# ideal_V2_0.net
KiCad netlist of a schematic drawn in Altium Designer
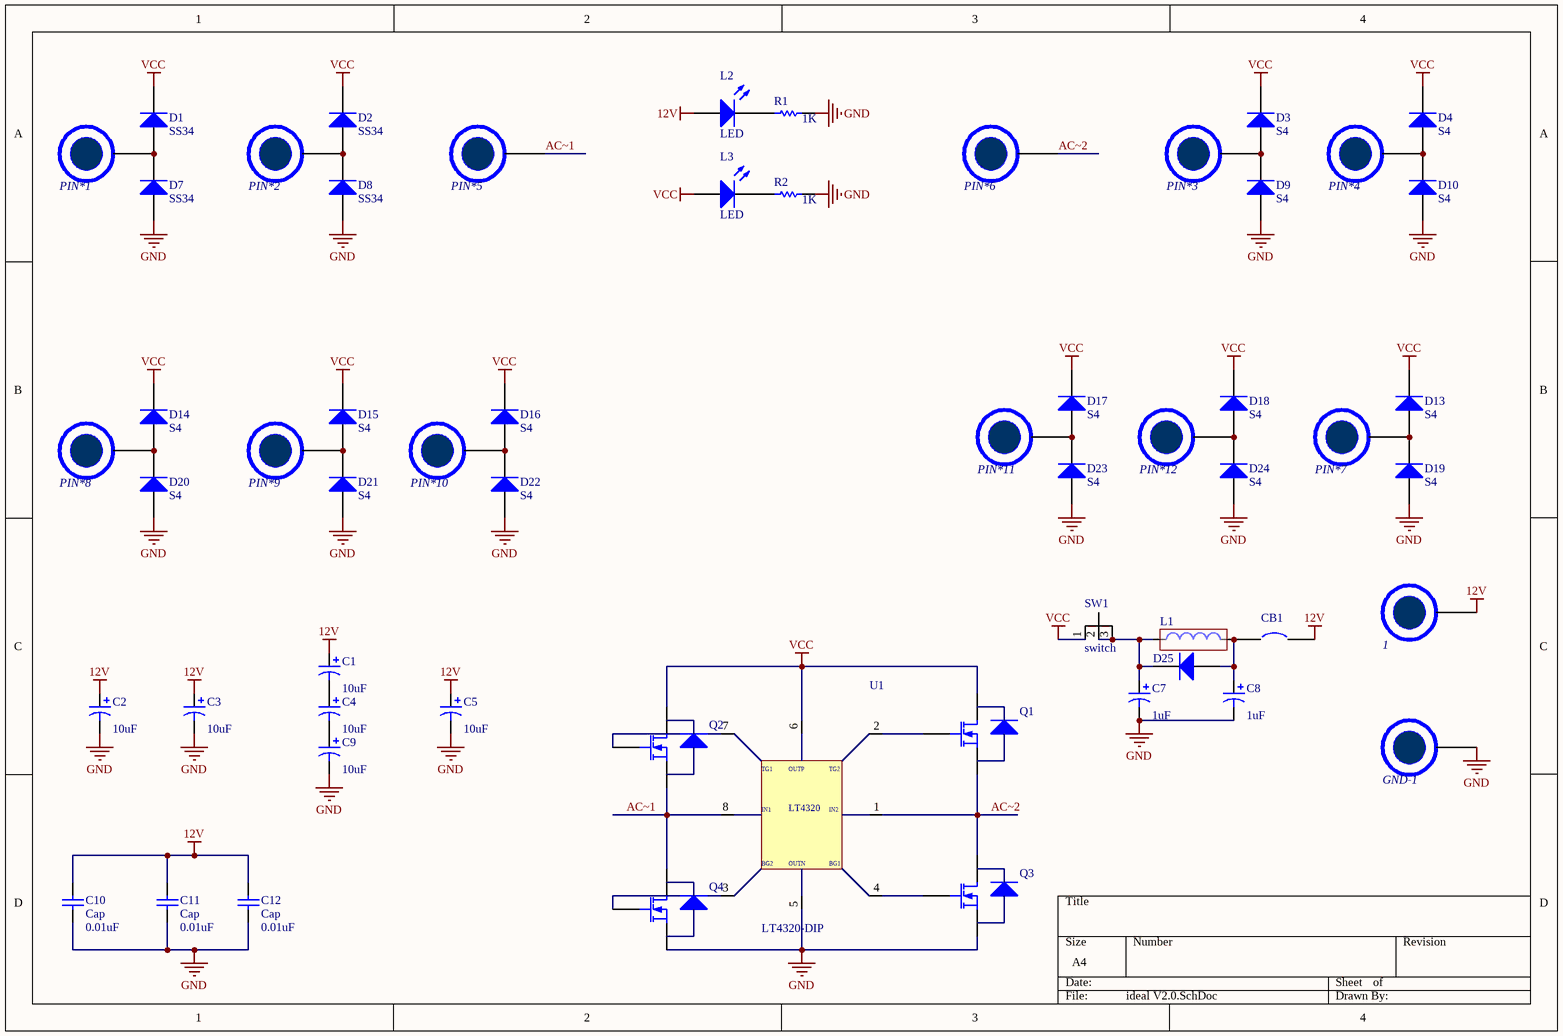
[diagram p0: ideal V2.0.SchDoc]

(export (version "E")
  (design (tool "Eeschema 10.0.6"))
  (components
    (comp (ref "1") (value "PIN") (footprint "PIN") (libsource (lib "常用元件库") (part "PIN")))
    (comp (ref "C1")
      (value "10uF")
      (footprint "法拉电容")
      (description "Polarized Capacitor (Radial)")
      (fields (field (name "Comment") "Cap Pol1") (field (name "PUBLISHER") "Altium Limited"))
      (libsource (lib "Miscellaneous Devices") (part "Cap Pol1"))
    )
    (comp (ref "C2")
      (value "10uF")
      (footprint "RB7.6-15")
      (description "Polarized Capacitor (Radial)")
      (fields (field (name "Comment") "Cap Pol1") (field (name "PUBLISHER") "Altium Limited"))
      (libsource (lib "Miscellaneous Devices") (part "Cap Pol1"))
    )
    (comp (ref "C3")
      (value "10uF")
      (footprint "RB7.6-15")
      (description "Polarized Capacitor (Radial)")
      (fields (field (name "Comment") "Cap Pol1") (field (name "PUBLISHER") "Altium Limited"))
      (libsource (lib "Miscellaneous Devices") (part "Cap Pol1"))
    )
    (comp (ref "C4")
      (value "10uF")
      (footprint "法拉电容")
      (description "Polarized Capacitor (Radial)")
      (fields (field (name "Comment") "Cap Pol1") (field (name "PUBLISHER") "Altium Limited"))
      (libsource (lib "Miscellaneous Devices") (part "Cap Pol1"))
    )
    (comp (ref "C5")
      (value "10uF")
      (footprint "RB7.6-15")
      (description "Polarized Capacitor (Radial)")
      (fields (field (name "Comment") "Cap Pol1") (field (name "PUBLISHER") "Altium Limited"))
      (libsource (lib "Miscellaneous Devices") (part "Cap Pol1"))
    )
    (comp (ref "C7")
      (value "1uF")
      (footprint "C2012")
      (description "Polarized Capacitor (Radial)")
      (fields (field (name "Comment") "Cap Pol1") (field (name "PUBLISHER") "Altium Limited"))
      (libsource (lib "Miscellaneous Devices") (part "Cap Pol1"))
    )
    (comp (ref "C8")
      (value "1uF")
      (footprint "C2012")
      (description "Polarized Capacitor (Radial)")
      (fields (field (name "Comment") "Cap Pol1") (field (name "PUBLISHER") "Altium Limited"))
      (libsource (lib "Miscellaneous Devices") (part "Cap Pol1"))
    )
    (comp (ref "C9")
      (value "10uF")
      (footprint "法拉电容")
      (description "Polarized Capacitor (Radial)")
      (fields (field (name "Comment") "Cap Pol1") (field (name "PUBLISHER") "Altium Limited"))
      (libsource (lib "Miscellaneous Devices") (part "Cap Pol1"))
    )
    (comp (ref "C10")
      (value "Cap")
      (footprint "C2012")
      (description "Capacitor")
      (fields (field (name "ALTIUM_VALUE") "0.01uF") (field (name "PUBLISHER") "Altium Limited"))
      (libsource (lib "Miscellaneous Devices") (part "Cap"))
    )
    (comp (ref "C11")
      (value "Cap")
      (footprint "C2012")
      (description "Capacitor")
      (fields (field (name "ALTIUM_VALUE") "0.01uF") (field (name "PUBLISHER") "Altium Limited"))
      (libsource (lib "Miscellaneous Devices") (part "Cap"))
    )
    (comp (ref "C12")
      (value "Cap")
      (footprint "C2012")
      (description "Capacitor")
      (fields (field (name "ALTIUM_VALUE") "0.01uF") (field (name "PUBLISHER") "Altium Limited"))
      (libsource (lib "Miscellaneous Devices") (part "Cap"))
    )
    (comp (ref "CB1")
      (value "Circuit Breaker")
      (footprint "SPST-2")
      (fields (field (name "PUBLISHER") "Altium Limited"))
      (libsource (lib "Miscellaneous Devices") (part "Circuit Breaker"))
    )
    (comp (ref "D1")
      (value "SS34")
      (footprint "1206(2)")
      (description "High Conductance Fast Diode")
      (fields (field (name "PUBLISHER") "Altium Limited"))
      (libsource (lib "K60-V4.0") (part "Diode 1N4148"))
    )
    (comp (ref "D2")
      (value "SS34")
      (footprint "1206(2)")
      (description "High Conductance Fast Diode")
      (fields (field (name "PUBLISHER") "Altium Limited"))
      (libsource (lib "K60-V4.0") (part "Diode 1N4148"))
    )
    (comp (ref "D3")
      (value "S4")
      (footprint "1206(2)")
      (description "High Conductance Fast Diode")
      (fields (field (name "PUBLISHER") "Altium Limited"))
      (libsource (lib "K60-V4.0") (part "Diode 1N4148"))
    )
    (comp (ref "D4")
      (value "S4")
      (footprint "1206(2)")
      (description "High Conductance Fast Diode")
      (fields (field (name "PUBLISHER") "Altium Limited"))
      (libsource (lib "K60-V4.0") (part "Diode 1N4148"))
    )
    (comp (ref "D7")
      (value "SS34")
      (footprint "1206(2)")
      (description "High Conductance Fast Diode")
      (fields (field (name "PUBLISHER") "Altium Limited"))
      (libsource (lib "K60-V4.0") (part "Diode 1N4148"))
    )
    (comp (ref "D8")
      (value "SS34")
      (footprint "1206(2)")
      (description "High Conductance Fast Diode")
      (fields (field (name "PUBLISHER") "Altium Limited"))
      (libsource (lib "K60-V4.0") (part "Diode 1N4148"))
    )
    (comp (ref "D9")
      (value "S4")
      (footprint "1206(2)")
      (description "High Conductance Fast Diode")
      (fields (field (name "PUBLISHER") "Altium Limited"))
      (libsource (lib "K60-V4.0") (part "Diode 1N4148"))
    )
    (comp (ref "D10")
      (value "S4")
      (footprint "1206(2)")
      (description "High Conductance Fast Diode")
      (fields (field (name "PUBLISHER") "Altium Limited"))
      (libsource (lib "K60-V4.0") (part "Diode 1N4148"))
    )
    (comp (ref "D13")
      (value "S4")
      (footprint "1206(2)")
      (description "High Conductance Fast Diode")
      (fields (field (name "PUBLISHER") "Altium Limited"))
      (libsource (lib "K60-V4.0") (part "Diode 1N4148"))
    )
    (comp (ref "D14")
      (value "S4")
      (footprint "1206(2)")
      (description "High Conductance Fast Diode")
      (fields (field (name "PUBLISHER") "Altium Limited"))
      (libsource (lib "K60-V4.0") (part "Diode 1N4148"))
    )
    (comp (ref "D15")
      (value "S4")
      (footprint "1206(2)")
      (description "High Conductance Fast Diode")
      (fields (field (name "PUBLISHER") "Altium Limited"))
      (libsource (lib "K60-V4.0") (part "Diode 1N4148"))
    )
    (comp (ref "D16")
      (value "S4")
      (footprint "1206(2)")
      (description "High Conductance Fast Diode")
      (fields (field (name "PUBLISHER") "Altium Limited"))
      (libsource (lib "K60-V4.0") (part "Diode 1N4148"))
    )
    (comp (ref "D17")
      (value "S4")
      (footprint "1206(2)")
      (description "High Conductance Fast Diode")
      (fields (field (name "PUBLISHER") "Altium Limited"))
      (libsource (lib "K60-V4.0") (part "Diode 1N4148"))
    )
    (comp (ref "D18")
      (value "S4")
      (footprint "1206(2)")
      (description "High Conductance Fast Diode")
      (fields (field (name "PUBLISHER") "Altium Limited"))
      (libsource (lib "K60-V4.0") (part "Diode 1N4148"))
    )
    (comp (ref "D19")
      (value "S4")
      (footprint "1206(2)")
      (description "High Conductance Fast Diode")
      (fields (field (name "PUBLISHER") "Altium Limited"))
      (libsource (lib "K60-V4.0") (part "Diode 1N4148"))
    )
    (comp (ref "D20")
      (value "S4")
      (footprint "1206(2)")
      (description "High Conductance Fast Diode")
      (fields (field (name "PUBLISHER") "Altium Limited"))
      (libsource (lib "K60-V4.0") (part "Diode 1N4148"))
    )
    (comp (ref "D21")
      (value "S4")
      (footprint "1206(2)")
      (description "High Conductance Fast Diode")
      (fields (field (name "PUBLISHER") "Altium Limited"))
      (libsource (lib "K60-V4.0") (part "Diode 1N4148"))
    )
    (comp (ref "D22")
      (value "S4")
      (footprint "1206(2)")
      (description "High Conductance Fast Diode")
      (fields (field (name "PUBLISHER") "Altium Limited"))
      (libsource (lib "K60-V4.0") (part "Diode 1N4148"))
    )
    (comp (ref "D23")
      (value "S4")
      (footprint "1206(2)")
      (description "High Conductance Fast Diode")
      (fields (field (name "PUBLISHER") "Altium Limited"))
      (libsource (lib "K60-V4.0") (part "Diode 1N4148"))
    )
    (comp (ref "D24")
      (value "S4")
      (footprint "1206(2)")
      (description "High Conductance Fast Diode")
      (fields (field (name "PUBLISHER") "Altium Limited"))
      (libsource (lib "K60-V4.0") (part "Diode 1N4148"))
    )
    (comp (ref "D25")
      (value "Diode 1N4001")
      (footprint "SK54")
      (description "1 Amp General Purpose Rectifier")
      (fields (field (name "PUBLISHER") "Altium Limited"))
      (libsource (lib "Miscellaneous Devices") (part "Diode 1N4001"))
    )
    (comp (ref "GND-1") (value "PIN") (footprint "PIN") (libsource (lib "常用元件库") (part "PIN")))
    (comp (ref "L1")
      (value "33uH")
      (footprint "SMD-EC-F16")
      (description "Inductor")
      (libsource (lib "Landzo") (part "Inductor"))
    )
    (comp (ref "L2") (value "LED") (footprint "C2012") (libsource (lib "Sparks") (part "LED")))
    (comp (ref "L3") (value "LED") (footprint "C2012") (libsource (lib "Sparks") (part "LED")))
    (comp (ref "PIN*1") (value "PIN") (footprint "PIN") (libsource (lib "2号库") (part "PIN")))
    (comp (ref "PIN*2") (value "PIN") (footprint "PIN") (libsource (lib "2号库") (part "PIN")))
    (comp (ref "PIN*3") (value "PIN") (footprint "PIN") (libsource (lib "2号库") (part "PIN")))
    (comp (ref "PIN*4") (value "PIN") (footprint "PIN") (libsource (lib "2号库") (part "PIN")))
    (comp (ref "PIN*5") (value "PIN") (footprint "PIN") (libsource (lib "2号库") (part "PIN")))
    (comp (ref "PIN*6") (value "PIN") (footprint "PIN") (libsource (lib "2号库") (part "PIN")))
    (comp (ref "PIN*7") (value "PIN") (footprint "PIN") (libsource (lib "2号库") (part "PIN")))
    (comp (ref "PIN*8") (value "PIN") (footprint "PIN") (libsource (lib "2号库") (part "PIN")))
    (comp (ref "PIN*9") (value "PIN") (footprint "PIN") (libsource (lib "2号库") (part "PIN")))
    (comp (ref "PIN*10") (value "PIN") (footprint "PIN") (libsource (lib "2号库") (part "PIN")))
    (comp (ref "PIN*11") (value "PIN") (footprint "PIN") (libsource (lib "2号库") (part "PIN")))
    (comp (ref "PIN*12") (value "PIN") (footprint "PIN") (libsource (lib "2号库") (part "PIN")))
    (comp (ref "Q1")
      (value "MOSFET-N")
      (footprint "mos")
      (description "N-Channel MOSFET")
      (fields (field (name "PUBLISHER") "Altium Limited"))
      (libsource (lib "原理图") (part "MOSFET-N"))
    )
    (comp (ref "Q2")
      (value "MOSFET-N")
      (footprint "mos")
      (description "N-Channel MOSFET")
      (fields (field (name "PUBLISHER") "Altium Limited"))
      (libsource (lib "原理图") (part "MOSFET-N"))
    )
    (comp (ref "Q3")
      (value "MOSFET-N")
      (footprint "mos")
      (description "N-Channel MOSFET")
      (fields (field (name "PUBLISHER") "Altium Limited"))
      (libsource (lib "原理图") (part "MOSFET-N"))
    )
    (comp (ref "Q4")
      (value "MOSFET-N")
      (footprint "mos")
      (description "N-Channel MOSFET")
      (fields (field (name "PUBLISHER") "Altium Limited"))
      (libsource (lib "原理图") (part "MOSFET-N"))
    )
    (comp (ref "R1")
      (value "1K")
      (footprint "R2012")
      (description "贴片电阻")
      (fields (field (name "Comment") "Res") (field (name "PUBLISHER") "Altium Limited"))
      (libsource (lib "Sparks") (part "Res"))
    )
    (comp (ref "R2")
      (value "1K")
      (footprint "R2012")
      (description "贴片电阻")
      (fields (field (name "Comment") "Res") (field (name "PUBLISHER") "Altium Limited"))
      (libsource (lib "Sparks") (part "Res"))
    )
    (comp (ref "SW1")
      (value "switch")
      (footprint "SW-125V6A(-)")
      (libsource (lib "2号库") (part "small switch"))
    )
    (comp (ref "U1") (value "LT4320-DIP") (footprint "DIP-8") (libsource (lib "2号库") (part "LT4320-DIP")))
  )
  (nets
    (net (code "1") (name "/AC~1") (class "Default")
      (node (ref "PIN*5") (pin "1") (pinfunction "PIN_1") (pintype "passive"))
      (node (ref "Q2") (pin "3") (pinfunction "S_3") (pintype "passive"))
      (node (ref "Q4") (pin "2") (pinfunction "D_2") (pintype "passive"))
      (node (ref "U1") (pin "8") (pinfunction "8_8") (pintype "passive"))
    )
    (net (code "2") (name "/AC~2") (class "Default")
      (node (ref "PIN*6") (pin "1") (pinfunction "PIN_1") (pintype "passive"))
      (node (ref "Q1") (pin "3") (pinfunction "S_3") (pintype "passive"))
      (node (ref "Q3") (pin "2") (pinfunction "D_2") (pintype "passive"))
      (node (ref "U1") (pin "1") (pinfunction "1_1") (pintype "passive"))
    )
    (net (code "3") (name "12V") (class "Default")
      (node (ref "1") (pin "1") (pinfunction "PIN_1") (pintype "passive"))
      (node (ref "C1") (pin "1") (pinfunction "1_1") (pintype "passive"))
      (node (ref "C10") (pin "2") (pinfunction "2_2") (pintype "passive"))
      (node (ref "C11") (pin "2") (pinfunction "2_2") (pintype "passive"))
      (node (ref "C12") (pin "2") (pinfunction "2_2") (pintype "passive"))
      (node (ref "C2") (pin "1") (pinfunction "1_1") (pintype "passive"))
      (node (ref "C3") (pin "1") (pinfunction "1_1") (pintype "passive"))
      (node (ref "C5") (pin "1") (pinfunction "1_1") (pintype "passive"))
      (node (ref "CB1") (pin "2") (pinfunction "2_2") (pintype "passive"))
      (node (ref "L2") (pin "1") (pinfunction "A_1") (pintype "passive"))
    )
    (net (code "4") (name "GND") (class "Default")
      (node (ref "C10") (pin "1") (pinfunction "1_1") (pintype "passive"))
      (node (ref "C11") (pin "1") (pinfunction "1_1") (pintype "passive"))
      (node (ref "C12") (pin "1") (pinfunction "1_1") (pintype "passive"))
      (node (ref "C2") (pin "2") (pinfunction "2_2") (pintype "passive"))
      (node (ref "C3") (pin "2") (pinfunction "2_2") (pintype "passive"))
      (node (ref "C5") (pin "2") (pinfunction "2_2") (pintype "passive"))
      (node (ref "C7") (pin "2") (pinfunction "2_2") (pintype "passive"))
      (node (ref "C8") (pin "2") (pinfunction "2_2") (pintype "passive"))
      (node (ref "C9") (pin "2") (pinfunction "2_2") (pintype "passive"))
      (node (ref "D10") (pin "1") (pinfunction "A_1") (pintype "passive"))
      (node (ref "D19") (pin "1") (pinfunction "A_1") (pintype "passive"))
      (node (ref "D20") (pin "1") (pinfunction "A_1") (pintype "passive"))
      (node (ref "D21") (pin "1") (pinfunction "A_1") (pintype "passive"))
      (node (ref "D22") (pin "1") (pinfunction "A_1") (pintype "passive"))
      (node (ref "D23") (pin "1") (pinfunction "A_1") (pintype "passive"))
      (node (ref "D24") (pin "1") (pinfunction "A_1") (pintype "passive"))
      (node (ref "D7") (pin "1") (pinfunction "A_1") (pintype "passive"))
      (node (ref "D8") (pin "1") (pinfunction "A_1") (pintype "passive"))
      (node (ref "D9") (pin "1") (pinfunction "A_1") (pintype "passive"))
      (node (ref "GND-1") (pin "1") (pinfunction "PIN_1") (pintype "passive"))
      (node (ref "Q3") (pin "3") (pinfunction "S_3") (pintype "passive"))
      (node (ref "Q4") (pin "3") (pinfunction "S_3") (pintype "passive"))
      (node (ref "R1") (pin "2") (pinfunction "2_2") (pintype "passive"))
      (node (ref "R2") (pin "2") (pinfunction "2_2") (pintype "passive"))
      (node (ref "U1") (pin "5") (pinfunction "5_5") (pintype "passive"))
    )
    (net (code "5") (name "Net-(C1-Pad2)") (class "Default")
      (node (ref "C1") (pin "2") (pinfunction "2_2") (pintype "passive"))
      (node (ref "C4") (pin "1") (pinfunction "1_1") (pintype "passive"))
    )
    (net (code "6") (name "Net-(C4-Pad2)") (class "Default")
      (node (ref "C4") (pin "2") (pinfunction "2_2") (pintype "passive"))
      (node (ref "C9") (pin "1") (pinfunction "1_1") (pintype "passive"))
    )
    (net (code "7") (name "Net-(D1-A)") (class "Default")
      (node (ref "D1") (pin "1") (pinfunction "A_1") (pintype "passive"))
      (node (ref "D7") (pin "2") (pinfunction "K_2") (pintype "passive"))
      (node (ref "PIN*1") (pin "1") (pinfunction "PIN_1") (pintype "passive"))
    )
    (net (code "8") (name "Net-(D2-A)") (class "Default")
      (node (ref "D2") (pin "1") (pinfunction "A_1") (pintype "passive"))
      (node (ref "D8") (pin "2") (pinfunction "K_2") (pintype "passive"))
      (node (ref "PIN*2") (pin "1") (pinfunction "PIN_1") (pintype "passive"))
    )
    (net (code "9") (name "Net-(D3-A)") (class "Default")
      (node (ref "D3") (pin "1") (pinfunction "A_1") (pintype "passive"))
      (node (ref "D9") (pin "2") (pinfunction "K_2") (pintype "passive"))
      (node (ref "PIN*3") (pin "1") (pinfunction "PIN_1") (pintype "passive"))
    )
    (net (code "10") (name "Net-(D10-K)") (class "Default")
      (node (ref "D10") (pin "2") (pinfunction "K_2") (pintype "passive"))
      (node (ref "D4") (pin "1") (pinfunction "A_1") (pintype "passive"))
      (node (ref "PIN*4") (pin "1") (pinfunction "PIN_1") (pintype "passive"))
    )
    (net (code "11") (name "Net-(D13-A)") (class "Default")
      (node (ref "D13") (pin "1") (pinfunction "A_1") (pintype "passive"))
      (node (ref "D19") (pin "2") (pinfunction "K_2") (pintype "passive"))
      (node (ref "PIN*7") (pin "1") (pinfunction "PIN_1") (pintype "passive"))
    )
    (net (code "12") (name "Net-(D14-A)") (class "Default")
      (node (ref "D14") (pin "1") (pinfunction "A_1") (pintype "passive"))
      (node (ref "D20") (pin "2") (pinfunction "K_2") (pintype "passive"))
      (node (ref "PIN*8") (pin "1") (pinfunction "PIN_1") (pintype "passive"))
    )
    (net (code "13") (name "Net-(D15-A)") (class "Default")
      (node (ref "D15") (pin "1") (pinfunction "A_1") (pintype "passive"))
      (node (ref "D21") (pin "2") (pinfunction "K_2") (pintype "passive"))
      (node (ref "PIN*9") (pin "1") (pinfunction "PIN_1") (pintype "passive"))
    )
    (net (code "14") (name "Net-(D16-A)") (class "Default")
      (node (ref "D16") (pin "1") (pinfunction "A_1") (pintype "passive"))
      (node (ref "D22") (pin "2") (pinfunction "K_2") (pintype "passive"))
      (node (ref "PIN*10") (pin "1") (pinfunction "PIN_1") (pintype "passive"))
    )
    (net (code "15") (name "Net-(D17-A)") (class "Default")
      (node (ref "D17") (pin "1") (pinfunction "A_1") (pintype "passive"))
      (node (ref "D23") (pin "2") (pinfunction "K_2") (pintype "passive"))
      (node (ref "PIN*11") (pin "1") (pinfunction "PIN_1") (pintype "passive"))
    )
    (net (code "16") (name "Net-(D18-A)") (class "Default")
      (node (ref "D18") (pin "1") (pinfunction "A_1") (pintype "passive"))
      (node (ref "D24") (pin "2") (pinfunction "K_2") (pintype "passive"))
      (node (ref "PIN*12") (pin "1") (pinfunction "PIN_1") (pintype "passive"))
    )
    (net (code "17") (name "Net-(D25-A)") (class "Default")
      (node (ref "C8") (pin "1") (pinfunction "1_1") (pintype "passive"))
      (node (ref "CB1") (pin "1") (pinfunction "1_1") (pintype "passive"))
      (node (ref "D25") (pin "1") (pinfunction "A_1") (pintype "passive"))
      (node (ref "L1") (pin "2") (pinfunction "2_2") (pintype "passive"))
    )
    (net (code "18") (name "Net-(D25-K)") (class "Default")
      (node (ref "C7") (pin "1") (pinfunction "1_1") (pintype "passive"))
      (node (ref "D25") (pin "2") (pinfunction "K_2") (pintype "passive"))
      (node (ref "L1") (pin "1") (pinfunction "1_1") (pintype "passive"))
      (node (ref "SW1") (pin "2") (pinfunction "2_2") (pintype "passive"))
      (node (ref "SW1") (pin "3") (pinfunction "3_3") (pintype "passive"))
    )
    (net (code "19") (name "Net-(L2-K)") (class "Default")
      (node (ref "L2") (pin "2") (pinfunction "K_2") (pintype "passive"))
      (node (ref "R1") (pin "1") (pinfunction "1_1") (pintype "passive"))
    )
    (net (code "20") (name "Net-(L3-K)") (class "Default")
      (node (ref "L3") (pin "2") (pinfunction "K_2") (pintype "passive"))
      (node (ref "R2") (pin "1") (pinfunction "1_1") (pintype "passive"))
    )
    (net (code "21") (name "Net-(Q1-G)") (class "Default")
      (node (ref "Q1") (pin "1") (pinfunction "G_1") (pintype "passive"))
      (node (ref "U1") (pin "2") (pinfunction "2_2") (pintype "passive"))
    )
    (net (code "22") (name "Net-(Q2-G)") (class "Default")
      (node (ref "Q2") (pin "1") (pinfunction "G_1") (pintype "passive"))
      (node (ref "U1") (pin "7") (pinfunction "7_7") (pintype "passive"))
    )
    (net (code "23") (name "Net-(Q3-G)") (class "Default")
      (node (ref "Q3") (pin "1") (pinfunction "G_1") (pintype "passive"))
      (node (ref "U1") (pin "4") (pinfunction "4_4") (pintype "passive"))
    )
    (net (code "24") (name "Net-(Q4-G)") (class "Default")
      (node (ref "Q4") (pin "1") (pinfunction "G_1") (pintype "passive"))
      (node (ref "U1") (pin "3") (pinfunction "3_3") (pintype "passive"))
    )
    (net (code "25") (name "VCC") (class "Default")
      (node (ref "D1") (pin "2") (pinfunction "K_2") (pintype "passive"))
      (node (ref "D13") (pin "2") (pinfunction "K_2") (pintype "passive"))
      (node (ref "D14") (pin "2") (pinfunction "K_2") (pintype "passive"))
      (node (ref "D15") (pin "2") (pinfunction "K_2") (pintype "passive"))
      (node (ref "D16") (pin "2") (pinfunction "K_2") (pintype "passive"))
      (node (ref "D17") (pin "2") (pinfunction "K_2") (pintype "passive"))
      (node (ref "D18") (pin "2") (pinfunction "K_2") (pintype "passive"))
      (node (ref "D2") (pin "2") (pinfunction "K_2") (pintype "passive"))
      (node (ref "D3") (pin "2") (pinfunction "K_2") (pintype "passive"))
      (node (ref "D4") (pin "2") (pinfunction "K_2") (pintype "passive"))
      (node (ref "L3") (pin "1") (pinfunction "A_1") (pintype "passive"))
      (node (ref "Q1") (pin "2") (pinfunction "D_2") (pintype "passive"))
      (node (ref "Q2") (pin "2") (pinfunction "D_2") (pintype "passive"))
      (node (ref "SW1") (pin "1") (pinfunction "1_1") (pintype "passive"))
      (node (ref "U1") (pin "6") (pinfunction "6_6") (pintype "passive"))
    )
  )
)
